# Charge_Discharge_Battery_Monitor_DC_DC_B.net
KiCad netlist of a schematic drawn in Altium Designer
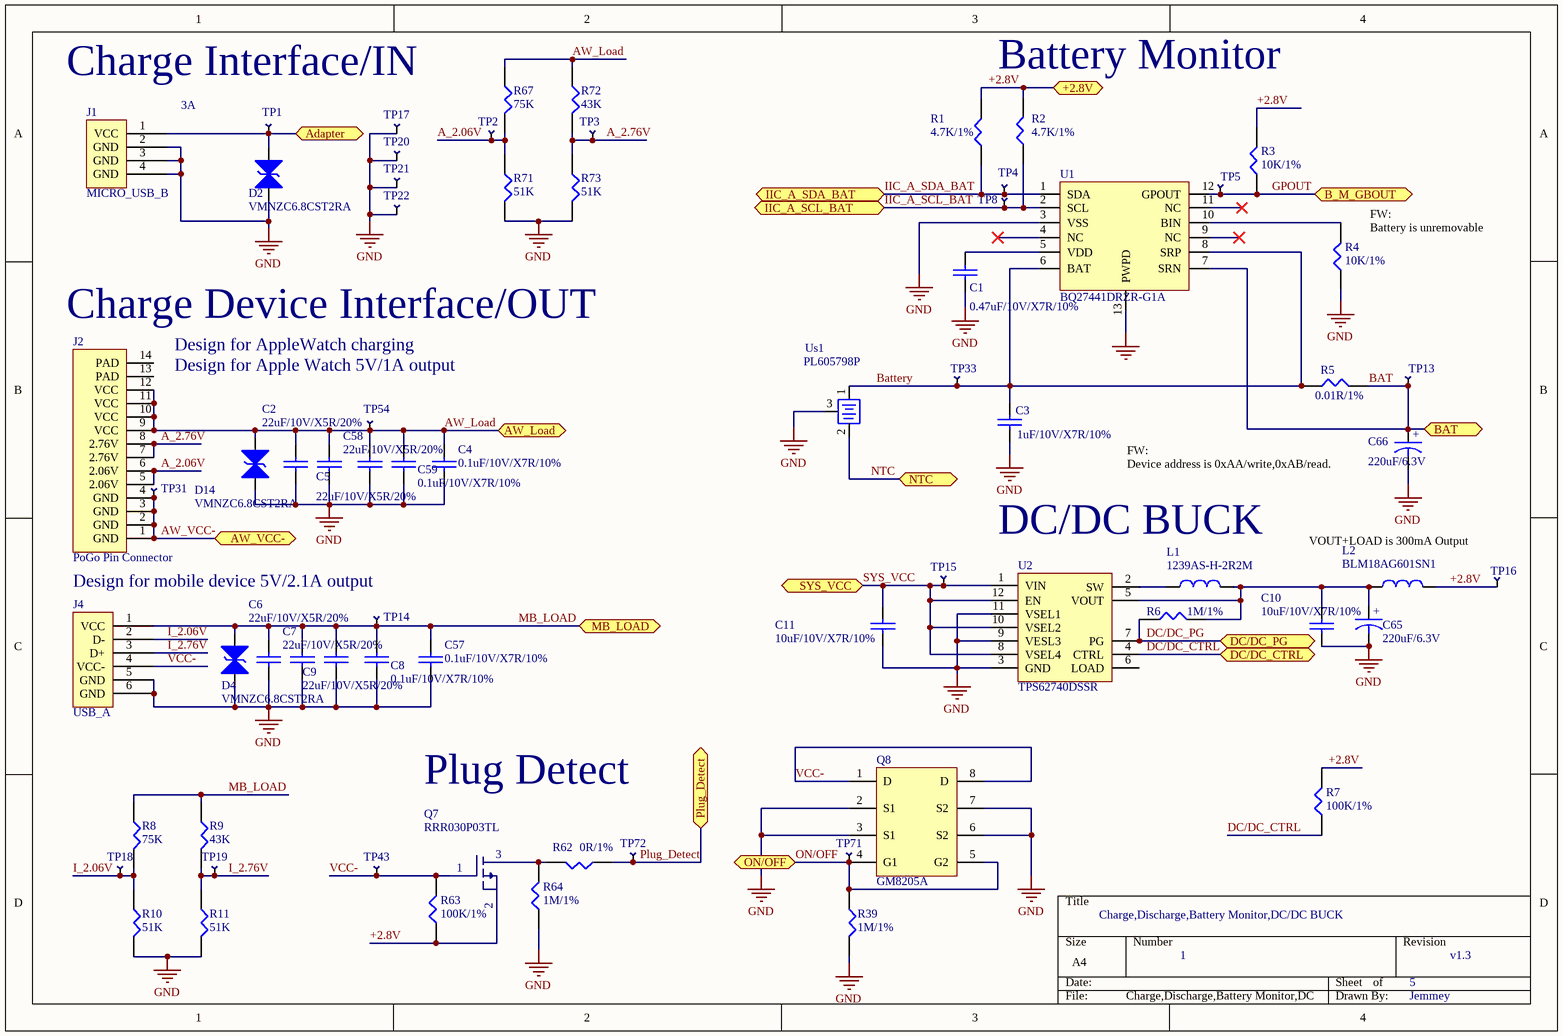
[diagram p0: Charge,Discharge,Battery Monitor,DC DC BUCK.SchDoc]

(export (version "E")
  (design (tool "Eeschema 10.0.6"))
  (components
    (comp (ref "C1")
      (value "0.47uF/10V/X7R/10%")
      (footprint "0402C")
      (description "厂家：Murata，型号：GRM155R71A474KE01D")
      (libsource (lib "*") (part "CAP"))
    )
    (comp (ref "C2")
      (value "22uF/10V/X5R/20%")
      (footprint "0603C")
      (description "厂家：Murata，型号：GRM188R61A226ME15D")
      (libsource (lib "*") (part "CAP"))
    )
    (comp (ref "C3")
      (value "1uF/10V/X7R/10%")
      (footprint "0402C")
      (description "厂家：Murata，型号：GRM155R61C105KA12D")
      (libsource (lib "*") (part "CAP"))
    )
    (comp (ref "C4")
      (value "0.1uF/10V/X7R/10%")
      (footprint "0402C")
      (description "厂家：Murata，型号：GRM155R71A104KA01D")
      (libsource (lib "*") (part "CAP"))
    )
    (comp (ref "C5")
      (value "22uF/10V/X5R/20%")
      (footprint "0603C")
      (description "厂家：Murata，型号：GRM188R61A226ME15D")
      (libsource (lib "*") (part "CAP"))
    )
    (comp (ref "C6")
      (value "22uF/10V/X5R/20%")
      (footprint "0603C")
      (description "厂家：Murata，型号：GRM188R61A226ME15D")
      (libsource (lib "*") (part "CAP"))
    )
    (comp (ref "C7")
      (value "22uF/10V/X5R/20%")
      (footprint "0603C")
      (description "厂家：Murata，型号：GRM188R61A226ME15D")
      (libsource (lib "*") (part "CAP"))
    )
    (comp (ref "C8")
      (value "0.1uF/10V/X7R/10%")
      (footprint "0402C")
      (description "厂家：Murata，型号：GRM155R71A104KA01D")
      (libsource (lib "*") (part "CAP"))
    )
    (comp (ref "C9")
      (value "22uF/10V/X5R/20%")
      (footprint "0603C")
      (description "厂家：Murata，型号：GRM188R61A226ME15D")
      (libsource (lib "*") (part "CAP"))
    )
    (comp (ref "C10")
      (value "10uF/10V/X7R/10%")
      (footprint "0603C")
      (description "厂家：Murata，型号：GRM188R61A106KE69D")
      (libsource (lib "*") (part "CAP"))
    )
    (comp (ref "C11")
      (value "10uF/10V/X7R/10%")
      (footprint "0603C")
      (description "厂家：Murata，型号：GRM188R61A106KE69D")
      (libsource (lib "*") (part "CAP"))
    )
    (comp (ref "C57")
      (value "0.1uF/10V/X7R/10%")
      (footprint "0402C")
      (description "厂家：Murata，型号：GRM155R71A104KA01D")
      (libsource (lib "*") (part "CAP"))
    )
    (comp (ref "C58")
      (value "22uF/10V/X5R/20%")
      (footprint "0603C")
      (description "厂家：Murata，型号：GRM188R61A226ME15D")
      (libsource (lib "*") (part "CAP"))
    )
    (comp (ref "C59")
      (value "0.1uF/10V/X7R/10%")
      (footprint "0402C")
      (description "厂家：Murata，型号：GRM155R71A104KA01D")
      (libsource (lib "*") (part "CAP"))
    )
    (comp (ref "C65")
      (value "220uF/6.3V")
      (footprint "3216")
      (description "厂家：ROHM，型号：TAJC227K010RNJ")
      (libsource (lib "MoJi LIB") (part "Capacitor"))
    )
    (comp (ref "C66")
      (value "220uF/6.3V")
      (footprint "3216")
      (description "厂家：ROHM，型号：TAJC227K010RNJ")
      (libsource (lib "MoJi LIB") (part "Capacitor"))
    )
    (comp (ref "D2")
      (value "VMNZC6.8CST2RA")
      (footprint "0402")
      (description "厂家：ROHM，型号：VMNZC6.8CST2RA")
      (libsource (lib "Amber") (part "ESD_1"))
    )
    (comp (ref "D4")
      (value "VMNZC6.8CST2RA")
      (footprint "0402")
      (description "厂家：ROHM，型号：VMNZC6.8CST2RA")
      (libsource (lib "Amber") (part "ESD_1"))
    )
    (comp (ref "D14")
      (value "VMNZC6.8CST2RA")
      (footprint "0402")
      (description "厂家：ROHM，型号：VMNZC6.8CST2RA")
      (libsource (lib "Amber") (part "ESD_1"))
    )
    (comp (ref "J1")
      (value "MICRO_USB_B")
      (footprint "Micro-USB-AVX-PAD")
      (description "厂家：AVX，型号：20-6751-005-001-007")
      (libsource (lib "Amber_Main_Board") (part "USB_B"))
    )
    (comp (ref "J2")
      (value "PoGo Pin Connector")
      (footprint "FPC_CON12-BACK-MOLEX")
      (description "厂家：MOLEX，型号：5034801200_sd")
      (libsource (lib "Amber_Main_Board") (part "PoGo Connector"))
    )
    (comp (ref "J4")
      (value "USB_A")
      (description "厂家：FCI，型号：87583")
      (libsource (lib "Amber_Main_Board") (part "USB_A"))
    )
    (comp (ref "L1")
      (value "1239AS-H-2R2M")
      (footprint "2520-TOKO")
      (description "厂家：Toko，型号1239AS-H-2R2M")
      (libsource (lib "Amber") (part "CHOKE"))
    )
    (comp (ref "L2")
      (value "BLM18AG601SN1")
      (footprint "0603R")
      (description "厂家：MURATA，型号：BLM18AG601SN1")
      (libsource (lib "Amber") (part "CHOKE"))
    )
    (comp (ref "Q7")
      (value "RRR030P03TL")
      (footprint "TSMT3")
      (description "厂家：ROHM，型号：RRR030P03TL")
      (libsource (lib "*") (part "PMOS"))
    )
    (comp (ref "Q8")
      (value "GM8205A")
      (footprint "TSSOP-8")
      (description "厂家：晶群科技，型号：GM8205A")
      (libsource (lib "Amber_Main_Board") (part "GM8205A"))
    )
    (comp (ref "R1")
      (value "4.7K/1%")
      (footprint "0402R")
      (description "厂家：Yageo，型号：RC0402FR-074K7L")
      (libsource (lib "*") (part "RES1"))
    )
    (comp (ref "R2")
      (value "4.7K/1%")
      (footprint "0402R")
      (description "厂家：Yageo，型号：RC0402FR-074K7L")
      (libsource (lib "*") (part "RES1"))
    )
    (comp (ref "R3")
      (value "10K/1%")
      (footprint "0402R")
      (description "厂家：Yageo，型号：RC0402FR-0710KL")
      (libsource (lib "*") (part "RES1"))
    )
    (comp (ref "R4")
      (value "10K/1%")
      (footprint "0402R")
      (description "厂家：Yageo，型号：RC0402FR-0710KL")
      (libsource (lib "*") (part "RES1"))
    )
    (comp (ref "R5")
      (value "0.01R/1%")
      (footprint "0805")
      (description "厂家：Yageo，型号：RL0805FR-070R01L")
      (libsource (lib "*") (part "RES1"))
    )
    (comp (ref "R6")
      (value "1M/1%")
      (footprint "0402R")
      (description "厂家：Yageo，型号：RC0402FR-071ML")
      (libsource (lib "*") (part "RES1"))
    )
    (comp (ref "R7")
      (value "100K/1%")
      (footprint "0402R")
      (description "厂家：Yageo，型号：RC0402FR-07100KL")
      (libsource (lib "*") (part "RES1"))
    )
    (comp (ref "R8")
      (value "75K")
      (footprint "0402R")
      (description "厂家：Yageo，型号：RC0402FR-0775KL")
      (libsource (lib "*") (part "RES1"))
    )
    (comp (ref "R9")
      (value "43K")
      (footprint "0402R")
      (description "厂家：Yageo，型号：RC0402FR-0743K9L")
      (libsource (lib "*") (part "RES1"))
    )
    (comp (ref "R10")
      (value "51K")
      (footprint "0402R")
      (description "厂家：Yageo，型号：RC0402FR-0751K9L")
      (libsource (lib "*") (part "RES1"))
    )
    (comp (ref "R11")
      (value "51K")
      (footprint "0402R")
      (description "厂家：Yageo，型号：RC0402FR-0751K9L")
      (libsource (lib "*") (part "RES1"))
    )
    (comp (ref "R39")
      (value "1M/1%")
      (footprint "0402R")
      (description "厂家：Yageo，型号：RC0402FR-071ML")
      (libsource (lib "*") (part "RES1"))
    )
    (comp (ref "R62")
      (value "0R/1%")
      (footprint "0402R")
      (description "厂家：Yageo，型号：RC0402FR-070RL")
      (libsource (lib "*") (part "RES1"))
    )
    (comp (ref "R63")
      (value "100K/1%")
      (footprint "0402R")
      (description "厂家：Yageo，型号：RC0402FR-07100KL")
      (libsource (lib "Schlib1") (part "RES"))
    )
    (comp (ref "R64")
      (value "1M/1%")
      (footprint "0402R")
      (description "厂家：Yageo，型号：RC0402FR-071ML")
      (libsource (lib "Schlib1") (part "RES"))
    )
    (comp (ref "R67")
      (value "75K")
      (footprint "0402R")
      (description "厂家：Yageo，型号：RC0402FR-0775KL")
      (libsource (lib "*") (part "RES1"))
    )
    (comp (ref "R71")
      (value "51K")
      (footprint "0402R")
      (description "厂家：Yageo，型号：RC0402FR-0751K9L")
      (libsource (lib "*") (part "RES1"))
    )
    (comp (ref "R72")
      (value "43K")
      (footprint "0402R")
      (description "厂家：Yageo，型号：RC0402FR-0743K9L")
      (libsource (lib "*") (part "RES1"))
    )
    (comp (ref "R73")
      (value "51K")
      (footprint "0402R")
      (description "厂家：Yageo，型号：RC0402FR-0751K9L")
      (libsource (lib "*") (part "RES1"))
    )
    (comp (ref "TP1")
      (value "TEST")
      (footprint "Test Pad")
      (description "Test Point")
      (libsource (lib "Amber") (part "TEST"))
    )
    (comp (ref "TP2")
      (value "TEST")
      (footprint "Test Pad")
      (description "Test Point")
      (libsource (lib "Amber") (part "TEST"))
    )
    (comp (ref "TP3")
      (value "TEST")
      (footprint "Test Pad")
      (description "Test Point")
      (libsource (lib "Amber") (part "TEST"))
    )
    (comp (ref "TP4")
      (value "TEST")
      (footprint "Test Pad")
      (description "Test Point")
      (libsource (lib "Amber") (part "TEST"))
    )
    (comp (ref "TP5")
      (value "TEST")
      (footprint "Test Pad")
      (description "Test Point")
      (libsource (lib "Amber") (part "TEST"))
    )
    (comp (ref "TP8")
      (value "TEST")
      (footprint "Test Pad")
      (description "Test Point")
      (libsource (lib "Amber") (part "TEST"))
    )
    (comp (ref "TP13")
      (value "TEST")
      (footprint "Test Pad")
      (description "Test Point")
      (libsource (lib "Amber") (part "TEST"))
    )
    (comp (ref "TP14")
      (value "TEST")
      (footprint "Test Pad")
      (description "Test Point")
      (libsource (lib "Amber") (part "TEST"))
    )
    (comp (ref "TP15")
      (value "TEST")
      (footprint "Test Pad")
      (description "Test Point")
      (libsource (lib "Amber") (part "TEST"))
    )
    (comp (ref "TP16")
      (value "TEST")
      (footprint "Test Pad")
      (description "Test Point")
      (libsource (lib "Amber") (part "TEST"))
    )
    (comp (ref "TP17")
      (value "TEST")
      (footprint "Test Pad")
      (description "Test Point")
      (libsource (lib "Amber") (part "TEST"))
    )
    (comp (ref "TP18")
      (value "TEST")
      (footprint "Test Pad")
      (description "Test Point")
      (libsource (lib "Amber") (part "TEST"))
    )
    (comp (ref "TP19")
      (value "TEST")
      (footprint "Test Pad")
      (description "Test Point")
      (libsource (lib "Amber") (part "TEST"))
    )
    (comp (ref "TP20")
      (value "TEST")
      (footprint "Test Pad")
      (description "Test Point")
      (libsource (lib "Amber") (part "TEST"))
    )
    (comp (ref "TP21")
      (value "TEST")
      (footprint "Test Pad")
      (description "Test Point")
      (libsource (lib "Amber") (part "TEST"))
    )
    (comp (ref "TP22")
      (value "TEST")
      (footprint "Test Pad")
      (description "Test Point")
      (libsource (lib "Amber") (part "TEST"))
    )
    (comp (ref "TP31")
      (value "TEST")
      (footprint "Test Pad")
      (description "Test Point")
      (libsource (lib "Amber") (part "TEST"))
    )
    (comp (ref "TP33")
      (value "TEST")
      (footprint "Test Pad")
      (description "Test Point")
      (libsource (lib "Amber") (part "TEST"))
    )
    (comp (ref "TP43")
      (value "TEST")
      (footprint "Test Pad")
      (description "Test Point")
      (libsource (lib "Amber") (part "TEST"))
    )
    (comp (ref "TP54")
      (value "TEST")
      (footprint "Test Pad")
      (description "Test Point")
      (libsource (lib "Amber") (part "TEST"))
    )
    (comp (ref "TP71")
      (value "TEST")
      (footprint "Test Pad")
      (description "Test Point")
      (libsource (lib "Amber") (part "TEST"))
    )
    (comp (ref "TP72")
      (value "TEST")
      (footprint "Test Pad")
      (description "Test Point")
      (libsource (lib "Amber") (part "TEST"))
    )
    (comp (ref "U1")
      (value "BQ27441DRZR-G1A")
      (footprint "DRZ")
      (description "厂家：TI，型号：BQ27441DRZR-G1A")
      (libsource (lib "Centrol Control Panel(20140910)") (part "Bq27411"))
    )
    (comp (ref "U2")
      (value "TPS62740DSSR")
      (footprint "DSS")
      (description "厂家：TI，型号：TPS62740DSSR")
      (libsource (lib "Amber") (part "TPS62740"))
    )
    (comp (ref "Us1")
      (value "PL605798P")
      (footprint "Battery")
      (description "厂家：红亚山，型号：PL605798P")
      (libsource (lib "Amber") (part "BAT"))
    )
  )
  (nets
    (net (code "1") (name "/+2.8V") (class "Default")
      (node (ref "L2") (pin "2") (pinfunction "2_2") (pintype "passive"))
      (node (ref "Q7") (pin "2") (pinfunction "S_2") (pintype "passive"))
      (node (ref "R1") (pin "2") (pinfunction "2_2") (pintype "passive"))
      (node (ref "R2") (pin "2") (pinfunction "2_2") (pintype "passive"))
      (node (ref "R3") (pin "2") (pinfunction "2_2") (pintype "passive"))
      (node (ref "R63") (pin "1") (pinfunction "1_1") (pintype "passive"))
      (node (ref "R7") (pin "2") (pinfunction "2_2") (pintype "passive"))
      (node (ref "TP16") (pin "1") (pinfunction "1_1") (pintype "passive"))
    )
    (net (code "2") (name "/AW_Load") (class "Default")
      (node (ref "C2") (pin "1") (pinfunction "1_1") (pintype "passive"))
      (node (ref "C4") (pin "1") (pinfunction "1_1") (pintype "passive"))
      (node (ref "C5") (pin "1") (pinfunction "1_1") (pintype "passive"))
      (node (ref "C58") (pin "1") (pinfunction "1_1") (pintype "passive"))
      (node (ref "C59") (pin "1") (pinfunction "1_1") (pintype "passive"))
      (node (ref "D14") (pin "2") (pinfunction "dIode2_2") (pintype "passive"))
      (node (ref "J2") (pin "10") (pinfunction "VCC_10") (pintype "passive"))
      (node (ref "J2") (pin "11") (pinfunction "VCC_11") (pintype "passive"))
      (node (ref "J2") (pin "12") (pinfunction "VCC_12") (pintype "passive"))
      (node (ref "J2") (pin "9") (pinfunction "VCC_9") (pintype "passive"))
      (node (ref "R67") (pin "1") (pinfunction "1_1") (pintype "passive"))
      (node (ref "R72") (pin "1") (pinfunction "1_1") (pintype "passive"))
      (node (ref "TP54") (pin "1") (pinfunction "1_1") (pintype "passive"))
    )
    (net (code "3") (name "/AW_VCC-") (class "Default")
      (node (ref "J2") (pin "1") (pinfunction "GND_1") (pintype "passive"))
      (node (ref "J2") (pin "2") (pinfunction "GND_2") (pintype "passive"))
      (node (ref "J2") (pin "3") (pinfunction "GND_3") (pintype "passive"))
      (node (ref "J2") (pin "4") (pinfunction "GND_4") (pintype "passive"))
      (node (ref "TP31") (pin "1") (pinfunction "1_1") (pintype "passive"))
    )
    (net (code "4") (name "/A_2.06V") (class "Default")
      (node (ref "J2") (pin "5") (pinfunction "2.06V_5") (pintype "passive"))
      (node (ref "J2") (pin "6") (pinfunction "2.06V_6") (pintype "passive"))
      (node (ref "R67") (pin "2") (pinfunction "2_2") (pintype "passive"))
      (node (ref "R71") (pin "1") (pinfunction "1_1") (pintype "passive"))
      (node (ref "TP2") (pin "1") (pinfunction "1_1") (pintype "passive"))
    )
    (net (code "5") (name "/A_2.76V") (class "Default")
      (node (ref "J2") (pin "7") (pinfunction "2.76V_7") (pintype "passive"))
      (node (ref "J2") (pin "8") (pinfunction "2.76V_8") (pintype "passive"))
      (node (ref "R72") (pin "2") (pinfunction "2_2") (pintype "passive"))
      (node (ref "R73") (pin "1") (pinfunction "1_1") (pintype "passive"))
      (node (ref "TP3") (pin "1") (pinfunction "1_1") (pintype "passive"))
    )
    (net (code "6") (name "/Adapter") (class "Default")
      (node (ref "D2") (pin "2") (pinfunction "dIode2_2") (pintype "passive"))
      (node (ref "J1") (pin "1") (pinfunction "VCC_1") (pintype "passive"))
      (node (ref "TP1") (pin "1") (pinfunction "1_1") (pintype "passive"))
    )
    (net (code "7") (name "/BAT") (class "Default")
      (node (ref "C66") (pin "1") (pinfunction "1_1") (pintype "passive"))
      (node (ref "R5") (pin "2") (pinfunction "2_2") (pintype "passive"))
      (node (ref "TP13") (pin "1") (pinfunction "1_1") (pintype "passive"))
      (node (ref "U1") (pin "7") (pinfunction "SRN_7") (pintype "passive"))
    )
    (net (code "8") (name "/Battery") (class "Default")
      (node (ref "C3") (pin "1") (pinfunction "1_1") (pintype "passive"))
      (node (ref "R5") (pin "1") (pinfunction "1_1") (pintype "passive"))
      (node (ref "TP33") (pin "1") (pinfunction "1_1") (pintype "passive"))
      (node (ref "U1") (pin "6") (pinfunction "BAT_6") (pintype "passive"))
      (node (ref "U1") (pin "8") (pinfunction "SRP_8") (pintype "passive"))
      (node (ref "Us1") (pin "1") (pinfunction "VCC_1") (pintype "passive"))
    )
    (net (code "9") (name "/DC{slash}DC_CTRL") (class "Default")
      (node (ref "R7") (pin "1") (pinfunction "1_1") (pintype "passive"))
      (node (ref "U2") (pin "4") (pinfunction "CTRL_4") (pintype "passive"))
    )
    (net (code "10") (name "/DC{slash}DC_PG") (class "Default")
      (node (ref "R6") (pin "1") (pinfunction "1_1") (pintype "passive"))
      (node (ref "U2") (pin "7") (pinfunction "PG_7") (pintype "passive"))
    )
    (net (code "11") (name "/GPOUT") (class "Default")
      (node (ref "R3") (pin "1") (pinfunction "1_1") (pintype "passive"))
      (node (ref "TP5") (pin "1") (pinfunction "1_1") (pintype "passive"))
      (node (ref "U1") (pin "12") (pinfunction "GPOUT_12") (pintype "passive"))
    )
    (net (code "12") (name "/IIC_A_SCL_BAT") (class "Default")
      (node (ref "R2") (pin "1") (pinfunction "1_1") (pintype "passive"))
      (node (ref "TP8") (pin "1") (pinfunction "1_1") (pintype "passive"))
      (node (ref "U1") (pin "2") (pinfunction "SCL_2") (pintype "passive"))
    )
    (net (code "13") (name "/IIC_A_SDA_BAT") (class "Default")
      (node (ref "R1") (pin "1") (pinfunction "1_1") (pintype "passive"))
      (node (ref "TP4") (pin "1") (pinfunction "1_1") (pintype "passive"))
      (node (ref "U1") (pin "1") (pinfunction "SDA_1") (pintype "passive"))
    )
    (net (code "14") (name "/I_2.06V") (class "Default")
      (node (ref "J4") (pin "2") (pinfunction "D-_2") (pintype "passive"))
      (node (ref "R10") (pin "1") (pinfunction "1_1") (pintype "passive"))
      (node (ref "R8") (pin "2") (pinfunction "2_2") (pintype "passive"))
      (node (ref "TP18") (pin "1") (pinfunction "1_1") (pintype "passive"))
    )
    (net (code "15") (name "/I_2.76V") (class "Default")
      (node (ref "J4") (pin "3") (pinfunction "D+_3") (pintype "passive"))
      (node (ref "R11") (pin "1") (pinfunction "1_1") (pintype "passive"))
      (node (ref "R9") (pin "2") (pinfunction "2_2") (pintype "passive"))
      (node (ref "TP19") (pin "1") (pinfunction "1_1") (pintype "passive"))
    )
    (net (code "16") (name "/MB_LOAD") (class "Default")
      (node (ref "C57") (pin "1") (pinfunction "1_1") (pintype "passive"))
      (node (ref "C6") (pin "1") (pinfunction "1_1") (pintype "passive"))
      (node (ref "C7") (pin "1") (pinfunction "1_1") (pintype "passive"))
      (node (ref "C8") (pin "1") (pinfunction "1_1") (pintype "passive"))
      (node (ref "C9") (pin "1") (pinfunction "1_1") (pintype "passive"))
      (node (ref "D4") (pin "2") (pinfunction "dIode2_2") (pintype "passive"))
      (node (ref "J4") (pin "1") (pinfunction "VCC_1") (pintype "passive"))
      (node (ref "R8") (pin "1") (pinfunction "1_1") (pintype "passive"))
      (node (ref "R9") (pin "1") (pinfunction "1_1") (pintype "passive"))
      (node (ref "TP14") (pin "1") (pinfunction "1_1") (pintype "passive"))
    )
    (net (code "17") (name "/NTC") (class "Default")
      (node (ref "Us1") (pin "2") (pinfunction "NTC_2") (pintype "passive"))
    )
    (net (code "18") (name "/ON{slash}OFF") (class "Default")
      (node (ref "Q8") (pin "4") (pinfunction "G1_4") (pintype "passive"))
      (node (ref "Q8") (pin "5") (pinfunction "G2_5") (pintype "passive"))
      (node (ref "R39") (pin "1") (pinfunction "1_1") (pintype "passive"))
      (node (ref "TP71") (pin "1") (pinfunction "1_1") (pintype "passive"))
    )
    (net (code "19") (name "/Plug_Detect") (class "Default")
      (node (ref "R62") (pin "1") (pinfunction "1_1") (pintype "passive"))
      (node (ref "TP72") (pin "1") (pinfunction "1_1") (pintype "passive"))
    )
    (net (code "20") (name "/SYS_VCC") (class "Default")
      (node (ref "C11") (pin "1") (pinfunction "1_1") (pintype "passive"))
      (node (ref "TP15") (pin "1") (pinfunction "1_1") (pintype "passive"))
      (node (ref "U2") (pin "1") (pinfunction "VIN_1") (pintype "passive"))
      (node (ref "U2") (pin "10") (pinfunction "VSEL2_10") (pintype "passive"))
      (node (ref "U2") (pin "12") (pinfunction "EN_12") (pintype "passive"))
      (node (ref "U2") (pin "8") (pinfunction "VSEL4_8") (pintype "passive"))
    )
    (net (code "21") (name "/VCC-") (class "Default")
      (node (ref "J4") (pin "4") (pinfunction "VCC-_4") (pintype "passive"))
      (node (ref "Q7") (pin "1") (pinfunction "G_1") (pintype "passive"))
      (node (ref "Q8") (pin "1") (pinfunction "D_1") (pintype "passive"))
      (node (ref "Q8") (pin "8") (pinfunction "D_8") (pintype "passive"))
      (node (ref "R63") (pin "2") (pinfunction "2_2") (pintype "passive"))
      (node (ref "TP43") (pin "1") (pinfunction "1_1") (pintype "passive"))
    )
    (net (code "22") (name "GND") (class "Default")
      (node (ref "C1") (pin "2") (pinfunction "2_2") (pintype "passive"))
      (node (ref "C10") (pin "2") (pinfunction "2_2") (pintype "passive"))
      (node (ref "C11") (pin "2") (pinfunction "2_2") (pintype "passive"))
      (node (ref "C2") (pin "2") (pinfunction "2_2") (pintype "passive"))
      (node (ref "C3") (pin "2") (pinfunction "2_2") (pintype "passive"))
      (node (ref "C4") (pin "2") (pinfunction "2_2") (pintype "passive"))
      (node (ref "C5") (pin "2") (pinfunction "2_2") (pintype "passive"))
      (node (ref "C57") (pin "2") (pinfunction "2_2") (pintype "passive"))
      (node (ref "C58") (pin "2") (pinfunction "2_2") (pintype "passive"))
      (node (ref "C59") (pin "2") (pinfunction "2_2") (pintype "passive"))
      (node (ref "C6") (pin "2") (pinfunction "2_2") (pintype "passive"))
      (node (ref "C65") (pin "2") (pinfunction "2_2") (pintype "passive"))
      (node (ref "C66") (pin "2") (pinfunction "2_2") (pintype "passive"))
      (node (ref "C7") (pin "2") (pinfunction "2_2") (pintype "passive"))
      (node (ref "C8") (pin "2") (pinfunction "2_2") (pintype "passive"))
      (node (ref "C9") (pin "2") (pinfunction "2_2") (pintype "passive"))
      (node (ref "D14") (pin "1") (pinfunction "Diode1_1") (pintype "passive"))
      (node (ref "D2") (pin "1") (pinfunction "Diode1_1") (pintype "passive"))
      (node (ref "D4") (pin "1") (pinfunction "Diode1_1") (pintype "passive"))
      (node (ref "J1") (pin "2") (pinfunction "GND_2") (pintype "passive"))
      (node (ref "J1") (pin "3") (pinfunction "GND_3") (pintype "passive"))
      (node (ref "J1") (pin "4") (pinfunction "GND_4") (pintype "passive"))
      (node (ref "J4") (pin "5") (pinfunction "GND_5") (pintype "passive"))
      (node (ref "J4") (pin "6") (pinfunction "GND_6") (pintype "passive"))
      (node (ref "Q8") (pin "2") (pinfunction "S1_2") (pintype "passive"))
      (node (ref "Q8") (pin "3") (pinfunction "S1_3") (pintype "passive"))
      (node (ref "Q8") (pin "6") (pinfunction "S2_6") (pintype "passive"))
      (node (ref "Q8") (pin "7") (pinfunction "S2_7") (pintype "passive"))
      (node (ref "R10") (pin "2") (pinfunction "2_2") (pintype "passive"))
      (node (ref "R11") (pin "2") (pinfunction "2_2") (pintype "passive"))
      (node (ref "R39") (pin "2") (pinfunction "2_2") (pintype "passive"))
      (node (ref "R4") (pin "1") (pinfunction "1_1") (pintype "passive"))
      (node (ref "R64") (pin "1") (pinfunction "1_1") (pintype "passive"))
      (node (ref "R71") (pin "2") (pinfunction "2_2") (pintype "passive"))
      (node (ref "R73") (pin "2") (pinfunction "2_2") (pintype "passive"))
      (node (ref "TP17") (pin "1") (pinfunction "1_1") (pintype "passive"))
      (node (ref "TP20") (pin "1") (pinfunction "1_1") (pintype "passive"))
      (node (ref "TP21") (pin "1") (pinfunction "1_1") (pintype "passive"))
      (node (ref "TP22") (pin "1") (pinfunction "1_1") (pintype "passive"))
      (node (ref "U1") (pin "13") (pinfunction "PWPD_13") (pintype "passive"))
      (node (ref "U1") (pin "3") (pinfunction "VSS_3") (pintype "passive"))
      (node (ref "U2") (pin "11") (pinfunction "VSEL1_11") (pintype "passive"))
      (node (ref "U2") (pin "3") (pinfunction "GND_3") (pintype "passive"))
      (node (ref "U2") (pin "9") (pinfunction "VESL3_9") (pintype "passive"))
      (node (ref "Us1") (pin "3") (pinfunction "GND_3") (pintype "passive"))
    )
    (net (code "23") (name "Net-(Q7-D)") (class "Default")
      (node (ref "Q7") (pin "3") (pinfunction "D_3") (pintype "passive"))
      (node (ref "R62") (pin "2") (pinfunction "2_2") (pintype "passive"))
      (node (ref "R64") (pin "2") (pinfunction "2_2") (pintype "passive"))
    )
    (net (code "24") (name "Net-(U1-BIN)") (class "Default")
      (node (ref "R4") (pin "2") (pinfunction "2_2") (pintype "passive"))
      (node (ref "U1") (pin "10") (pinfunction "BIN_10") (pintype "passive"))
    )
    (net (code "25") (name "Net-(U1-VDD)") (class "Default")
      (node (ref "C1") (pin "1") (pinfunction "1_1") (pintype "passive"))
      (node (ref "U1") (pin "5") (pinfunction "VDD_5") (pintype "passive"))
    )
    (net (code "26") (name "Net-(U2-SW)") (class "Default")
      (node (ref "L1") (pin "1") (pinfunction "1_1") (pintype "passive"))
      (node (ref "U2") (pin "2") (pinfunction "SW_2") (pintype "passive"))
    )
    (net (code "27") (name "Net-(U2-VOUT)") (class "Default")
      (node (ref "C10") (pin "1") (pinfunction "1_1") (pintype "passive"))
      (node (ref "C65") (pin "1") (pinfunction "1_1") (pintype "passive"))
      (node (ref "L1") (pin "2") (pinfunction "2_2") (pintype "passive"))
      (node (ref "L2") (pin "1") (pinfunction "1_1") (pintype "passive"))
      (node (ref "R6") (pin "2") (pinfunction "2_2") (pintype "passive"))
      (node (ref "U2") (pin "5") (pinfunction "VOUT_5") (pintype "passive"))
    )
    (net (code "28") (name "unconnected-(J2-PAD-Pad13)") (class "Default")
      (node (ref "J2") (pin "13") (pinfunction "PAD_13") (pintype "passive"))
    )
    (net (code "29") (name "unconnected-(J2-PAD-Pad14)") (class "Default")
      (node (ref "J2") (pin "14") (pinfunction "PAD_14") (pintype "passive"))
    )
    (net (code "30") (name "unconnected-(U1-NC-Pad4)") (class "Default")
      (node (ref "U1") (pin "4") (pinfunction "NC_4") (pintype "passive+no_connect"))
    )
    (net (code "31") (name "unconnected-(U1-NC-Pad9)") (class "Default")
      (node (ref "U1") (pin "9") (pinfunction "NC_9") (pintype "passive+no_connect"))
    )
    (net (code "32") (name "unconnected-(U1-NC-Pad11)") (class "Default")
      (node (ref "U1") (pin "11") (pinfunction "NC_11") (pintype "passive+no_connect"))
    )
    (net (code "33") (name "unconnected-(U2-LOAD-Pad6)") (class "Default")
      (node (ref "U2") (pin "6") (pinfunction "LOAD_6") (pintype "passive"))
    )
  )
)
